# 1_POWER.net
KiCad netlist of a schematic drawn in Altium Designer
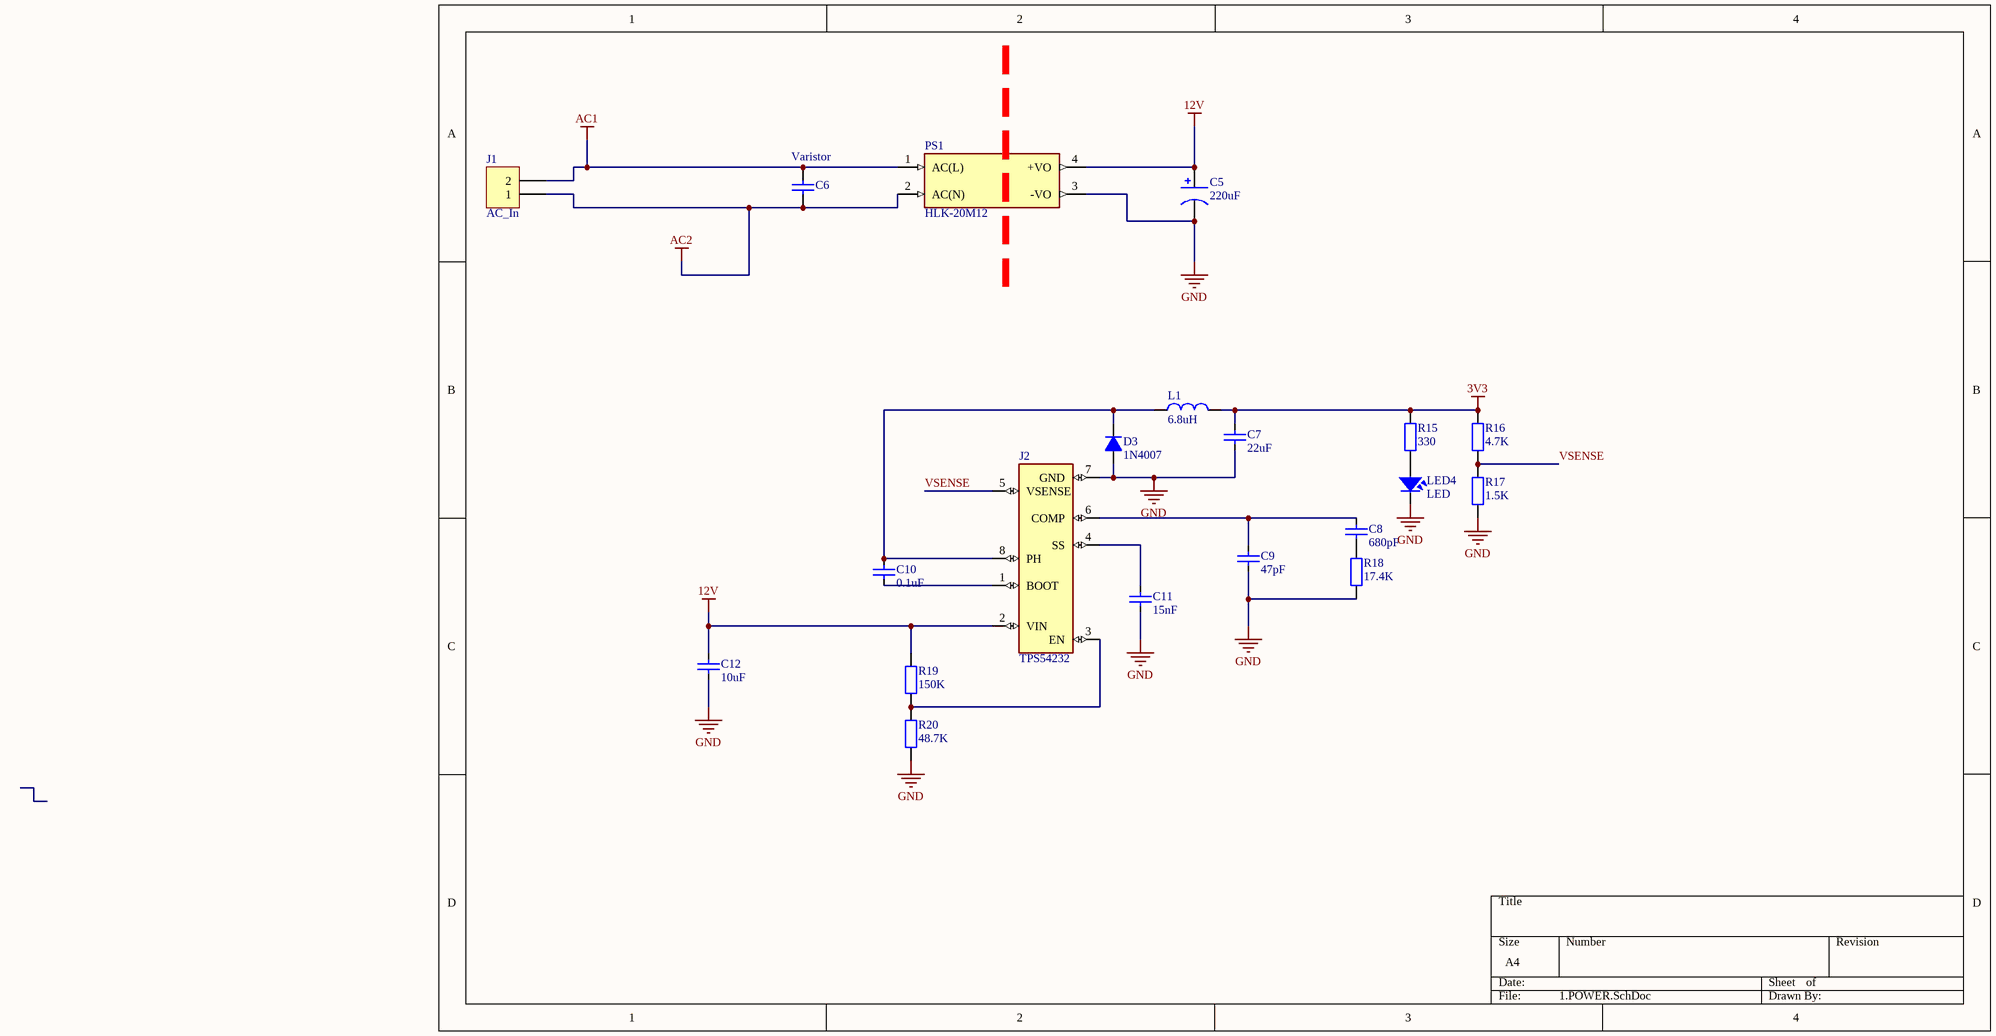
[diagram p0: 1.POWER.SchDoc]

(export (version "E")
  (design (tool "Eeschema 10.0.6"))
  (components
    (comp (ref "C5")
      (value "220uF")
      (footprint "C3MM")
      (description "Polarized Capacitor (Axial)")
      (fields (field (name "PUBLISHER") "Altium Limited"))
      (libsource (lib "Main") (part "Cap Pol"))
    )
    (comp (ref "C6")
      (value "Varistor")
      (footprint "CAP_CERAMIC")
      (description "Capacitor")
      (fields (field (name "PUBLISHER") "Altium Limited"))
      (libsource (lib "Main") (part "CapCeramic"))
    )
    (comp (ref "C7")
      (value "22uF")
      (footprint "CAP_0805")
      (description "Capacitor")
      (fields (field (name "PUBLISHER") "Altium Limited"))
      (libsource (lib "Main") (part "CapSMD"))
    )
    (comp (ref "C8")
      (value "680pF")
      (footprint "CAP_0805")
      (description "Capacitor")
      (fields (field (name "PUBLISHER") "Altium Limited"))
      (libsource (lib "Main") (part "CapSMD"))
    )
    (comp (ref "C9")
      (value "47pF")
      (footprint "CAP_0805")
      (description "Capacitor")
      (fields (field (name "PUBLISHER") "Altium Limited"))
      (libsource (lib "Main") (part "CapSMD"))
    )
    (comp (ref "C10")
      (value "0.1uF")
      (footprint "CAP_0805")
      (description "Capacitor")
      (fields (field (name "PUBLISHER") "Altium Limited"))
      (libsource (lib "Main") (part "CapSMD"))
    )
    (comp (ref "C11")
      (value "15nF")
      (footprint "CAP_0805")
      (description "Capacitor")
      (fields (field (name "PUBLISHER") "Altium Limited"))
      (libsource (lib "Main") (part "CapSMD"))
    )
    (comp (ref "C12")
      (value "10uF")
      (footprint "CAP_0805")
      (description "Capacitor")
      (fields (field (name "PUBLISHER") "Altium Limited"))
      (libsource (lib "Main") (part "CapSMD"))
    )
    (comp (ref "D3")
      (value "1N4007")
      (footprint "DIO-214AC(SMA)")
      (description "Diode 1A")
      (libsource (lib "Main") (part "D1A"))
    )
    (comp (ref "J1")
      (value "AC_In")
      (footprint "KF2-5.08T")
      (fields
        (field (name "MANUFACTURER") "Würth Elektronik eiSos GmbH")
        (field (name "PARTNO") "691103110002")
        (field (name "CREATED BY") "Karrer Zheng")
      )
      (libsource (lib "Main") (part "KF2"))
    )
    (comp (ref "J2")
      (value "TPS54232")
      (footprint "SOIC8")
      (description "Buck Switching Regulator IC Positive Adjustable 0.8V 1 Output 2A 8-SOIC (0.154, 3.90mm Width)")
      (fields (field (name "MF") "Texas Instruments"))
      (libsource (lib "TPS54232") (part "TPS54232"))
    )
    (comp (ref "L1")
      (value "6.8uH")
      (footprint "L-SMD-M-12x10")
      (description "Inductor")
      (libsource (lib "Main") (part "Inductor"))
    )
    (comp (ref "LED4")
      (value "LED")
      (footprint "LED_RED_SMD_0805")
      (description "LED Single colour Green and Red")
      (libsource (lib "Main") (part "LED"))
    )
    (comp (ref "PS1")
      (value "HLK-20M12")
      (footprint "CONV_HLK-20M12")
      (description "20W ultra-small series module power supply")
      (fields (field (name "MF") "Hi-link"))
      (libsource (lib "HLK-20M12") (part "HLK-20M12"))
    )
    (comp (ref "R15")
      (value "330")
      (footprint "RES-SMD-0805")
      (description "Resistor SMD")
      (fields
        (field (name "MANUFACTURER") "Generic Components")
        (field (name "PUBLISHER") "Altium Hobart Technology Centre")
      )
      (libsource (lib "Main") (part "Resistor - SMD"))
    )
    (comp (ref "R16")
      (value "4.7K")
      (footprint "RES-SMD-0805")
      (description "Resistor SMD")
      (fields
        (field (name "MANUFACTURER") "Generic Components")
        (field (name "PUBLISHER") "Altium Hobart Technology Centre")
      )
      (libsource (lib "Main") (part "Resistor - SMD"))
    )
    (comp (ref "R17")
      (value "1.5K")
      (footprint "RES-SMD-0805")
      (description "Resistor SMD")
      (fields
        (field (name "MANUFACTURER") "Generic Components")
        (field (name "PUBLISHER") "Altium Hobart Technology Centre")
      )
      (libsource (lib "Main") (part "Resistor - SMD"))
    )
    (comp (ref "R18")
      (value "17.4K")
      (footprint "RES-SMD-0805")
      (description "Resistor SMD")
      (fields
        (field (name "MANUFACTURER") "Generic Components")
        (field (name "PUBLISHER") "Altium Hobart Technology Centre")
      )
      (libsource (lib "Main") (part "Resistor - SMD"))
    )
    (comp (ref "R19")
      (value "150K")
      (footprint "RES-SMD-0805")
      (description "Resistor SMD")
      (fields
        (field (name "MANUFACTURER") "Generic Components")
        (field (name "PUBLISHER") "Altium Hobart Technology Centre")
      )
      (libsource (lib "Main") (part "Resistor - SMD"))
    )
    (comp (ref "R20")
      (value "48.7K")
      (footprint "RES-SMD-0805")
      (description "Resistor SMD")
      (fields
        (field (name "MANUFACTURER") "Generic Components")
        (field (name "PUBLISHER") "Altium Hobart Technology Centre")
      )
      (libsource (lib "Main") (part "Resistor - SMD"))
    )
  )
  (nets
    (net (code "1") (name "/VSENSE") (class "Default")
      (node (ref "J2") (pin "5") (pinfunction "VSENSE_5") (pintype "bidirectional"))
      (node (ref "R16") (pin "1") (pinfunction "1_1") (pintype "passive"))
      (node (ref "R17") (pin "2") (pinfunction "2_2") (pintype "passive"))
    )
    (net (code "2") (name "3V3") (class "Default")
      (node (ref "C7") (pin "1") (pinfunction "1_1") (pintype "passive"))
      (node (ref "L1") (pin "2") (pinfunction "2_2") (pintype "passive"))
      (node (ref "R15") (pin "2") (pinfunction "2_2") (pintype "passive"))
      (node (ref "R16") (pin "2") (pinfunction "2_2") (pintype "passive"))
    )
    (net (code "3") (name "12V") (class "Default")
      (node (ref "C12") (pin "1") (pinfunction "1_1") (pintype "passive"))
      (node (ref "C5") (pin "1") (pinfunction "1_1") (pintype "passive"))
      (node (ref "J2") (pin "2") (pinfunction "VIN_2") (pintype "bidirectional"))
      (node (ref "PS1") (pin "4") (pinfunction "+VO_4") (pintype "output"))
      (node (ref "R19") (pin "2") (pinfunction "2_2") (pintype "passive"))
    )
    (net (code "4") (name "AC1") (class "Default")
      (node (ref "C6") (pin "1") (pinfunction "1_1") (pintype "passive"))
      (node (ref "J1") (pin "2") (pinfunction "2_2") (pintype "passive"))
      (node (ref "PS1") (pin "1") (pinfunction "AC(L)_1") (pintype "input"))
    )
    (net (code "5") (name "AC2") (class "Default")
      (node (ref "C6") (pin "2") (pinfunction "2_2") (pintype "passive"))
      (node (ref "J1") (pin "1") (pinfunction "1_1") (pintype "passive"))
      (node (ref "PS1") (pin "2") (pinfunction "AC(N)_2") (pintype "input"))
    )
    (net (code "6") (name "GND") (class "Default")
      (node (ref "C11") (pin "2") (pinfunction "2_2") (pintype "passive"))
      (node (ref "C12") (pin "2") (pinfunction "2_2") (pintype "passive"))
      (node (ref "C5") (pin "2") (pinfunction "2_2") (pintype "passive"))
      (node (ref "C7") (pin "2") (pinfunction "2_2") (pintype "passive"))
      (node (ref "C9") (pin "2") (pinfunction "2_2") (pintype "passive"))
      (node (ref "D3") (pin "1") (pinfunction "A_1") (pintype "passive"))
      (node (ref "J2") (pin "7") (pinfunction "GND_7") (pintype "bidirectional"))
      (node (ref "LED4") (pin "2") (pinfunction "2_2") (pintype "passive"))
      (node (ref "PS1") (pin "3") (pinfunction "-VO_3") (pintype "output"))
      (node (ref "R17") (pin "1") (pinfunction "1_1") (pintype "passive"))
      (node (ref "R18") (pin "1") (pinfunction "1_1") (pintype "passive"))
      (node (ref "R20") (pin "1") (pinfunction "1_1") (pintype "passive"))
    )
    (net (code "7") (name "Net-(C8-Pad2)") (class "Default")
      (node (ref "C8") (pin "2") (pinfunction "2_2") (pintype "passive"))
      (node (ref "R18") (pin "2") (pinfunction "2_2") (pintype "passive"))
    )
    (net (code "8") (name "Net-(D3-K)") (class "Default")
      (node (ref "C10") (pin "1") (pinfunction "1_1") (pintype "passive"))
      (node (ref "D3") (pin "2") (pinfunction "K_2") (pintype "passive"))
      (node (ref "J2") (pin "8") (pinfunction "PH_8") (pintype "bidirectional"))
      (node (ref "L1") (pin "1") (pinfunction "1_1") (pintype "passive"))
    )
    (net (code "9") (name "Net-(J2-BOOT)") (class "Default")
      (node (ref "C10") (pin "2") (pinfunction "2_2") (pintype "passive"))
      (node (ref "J2") (pin "1") (pinfunction "BOOT_1") (pintype "bidirectional"))
    )
    (net (code "10") (name "Net-(J2-COMP)") (class "Default")
      (node (ref "C8") (pin "1") (pinfunction "1_1") (pintype "passive"))
      (node (ref "C9") (pin "1") (pinfunction "1_1") (pintype "passive"))
      (node (ref "J2") (pin "6") (pinfunction "COMP_6") (pintype "bidirectional"))
    )
    (net (code "11") (name "Net-(J2-EN)") (class "Default")
      (node (ref "J2") (pin "3") (pinfunction "EN_3") (pintype "bidirectional"))
      (node (ref "R19") (pin "1") (pinfunction "1_1") (pintype "passive"))
      (node (ref "R20") (pin "2") (pinfunction "2_2") (pintype "passive"))
    )
    (net (code "12") (name "Net-(J2-SS)") (class "Default")
      (node (ref "C11") (pin "1") (pinfunction "1_1") (pintype "passive"))
      (node (ref "J2") (pin "4") (pinfunction "SS_4") (pintype "bidirectional"))
    )
    (net (code "13") (name "Net-(LED4-Pad1)") (class "Default")
      (node (ref "LED4") (pin "1") (pinfunction "1_1") (pintype "passive"))
      (node (ref "R15") (pin "1") (pinfunction "1_1") (pintype "passive"))
    )
  )
)
